# ESP_Grow_Main_V2_2_Pump_NeoPixel.net
KiCad netlist of a schematic drawn in Altium Designer
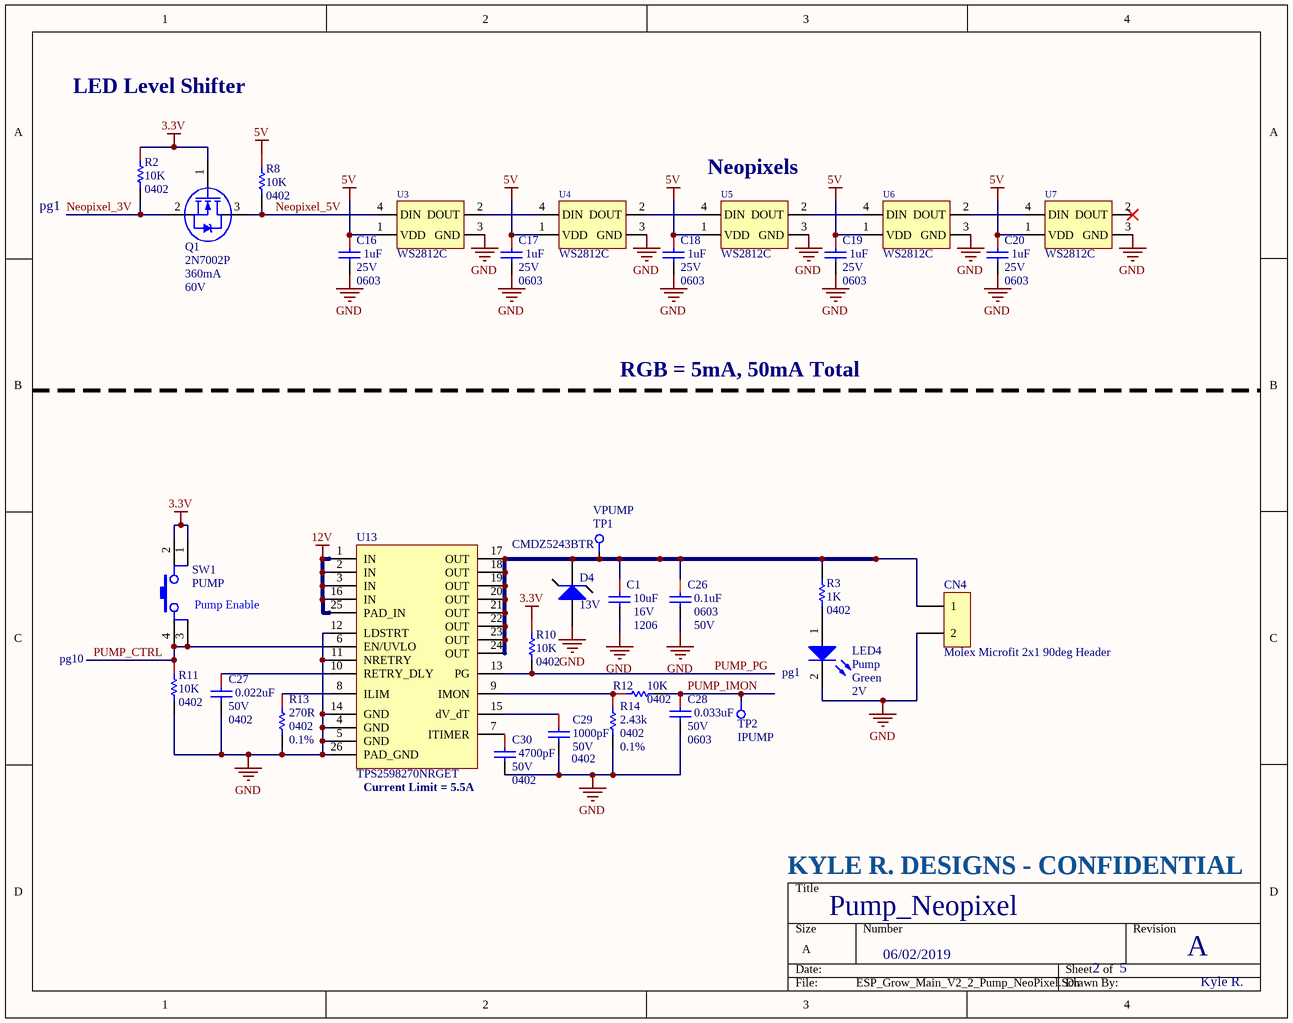
[diagram p0: ESP_Grow_Main_V2_2_Pump_NeoPixel.SchDoc]

(export (version "E")
  (design (tool "Eeschema 10.0.6"))
  (components
    (comp (ref "C1")
      (value "10uF")
      (footprint "CAPC1206(3216)_M")
      (fields (field (name "VOLTAGE - RATED") "16V") (field (name "PACKAGE") "1206"))
      (libsource (lib "Kyle-Passive") (part "CAP CER 10UF 16V 1206"))
    )
    (comp (ref "C16")
      (value "1uF")
      (footprint "CAPC0603(1608)_N")
      (description "1uF 0603 25V")
      (fields
        (field (name "MANUFACTURER") "TDK Corporation")
        (field (name "MANUFACTURER PART NUMBER") "CGA3E1X7R1E105K080AC")
        (field (name "VOLTAGE - RATED") "25V")
        (field (name "PACKAGE / CASE") "0603")
      )
      (libsource (lib "OLogic-Passive") (part "CAP CER 1UF 25V 10% X7R 0603"))
    )
    (comp (ref "C17")
      (value "1uF")
      (footprint "CAPC0603(1608)_N")
      (description "1uF 0603 25V")
      (fields
        (field (name "MANUFACTURER") "TDK Corporation")
        (field (name "MANUFACTURER PART NUMBER") "CGA3E1X7R1E105K080AC")
        (field (name "VOLTAGE - RATED") "25V")
        (field (name "PACKAGE / CASE") "0603")
      )
      (libsource (lib "OLogic-Passive") (part "CAP CER 1UF 25V 10% X7R 0603"))
    )
    (comp (ref "C18")
      (value "1uF")
      (footprint "CAPC0603(1608)_N")
      (description "1uF 0603 25V")
      (fields
        (field (name "MANUFACTURER") "TDK Corporation")
        (field (name "MANUFACTURER PART NUMBER") "CGA3E1X7R1E105K080AC")
        (field (name "VOLTAGE - RATED") "25V")
        (field (name "PACKAGE / CASE") "0603")
      )
      (libsource (lib "OLogic-Passive") (part "CAP CER 1UF 25V 10% X7R 0603"))
    )
    (comp (ref "C19")
      (value "1uF")
      (footprint "CAPC0603(1608)_N")
      (description "1uF 0603 25V")
      (fields
        (field (name "MANUFACTURER") "TDK Corporation")
        (field (name "MANUFACTURER PART NUMBER") "CGA3E1X7R1E105K080AC")
        (field (name "VOLTAGE - RATED") "25V")
        (field (name "PACKAGE / CASE") "0603")
      )
      (libsource (lib "OLogic-Passive") (part "CAP CER 1UF 25V 10% X7R 0603"))
    )
    (comp (ref "C20")
      (value "1uF")
      (footprint "CAPC0603(1608)_N")
      (description "1uF 0603 25V")
      (fields
        (field (name "MANUFACTURER") "TDK Corporation")
        (field (name "MANUFACTURER PART NUMBER") "CGA3E1X7R1E105K080AC")
        (field (name "VOLTAGE - RATED") "25V")
        (field (name "PACKAGE / CASE") "0603")
      )
      (libsource (lib "OLogic-Passive") (part "CAP CER 1UF 25V 10% X7R 0603"))
    )
    (comp (ref "C26")
      (value "0.1uF")
      (footprint "CAPC0603(1608)_L")
      (description "100NF 50V 0603")
      (fields
        (field (name "MANUFACTURER") "YAGEO")
        (field (name "MANUFACTURER PART NUMBER") "CC0603KRX7R9BB104")
        (field (name "CAPACITANCE") "0.1uF")
        (field (name "PACKAGE / CASE") "0603")
        (field (name "VOLTAGE - RATED") "50V")
      )
      (libsource (lib "JLCPCB_Capacitors") (part "0.1uF_0603"))
    )
    (comp (ref "C27")
      (value "0.022uF")
      (footprint "CAPC0402(1005)_N")
      (description "CAP CER 0.022UF 50V X7R 0402")
      (fields
        (field (name "VOLTAGE (RATED)") "50V")
        (field (name "PACKAGE (IMPERIAL)") "0402")
        (field (name "TOLERANCE") "10%")
      )
      (libsource (lib "OLogic Nexus Vault") (part "=Capacitance"))
    )
    (comp (ref "C28")
      (value "0.033uF")
      (footprint "CAPC0603(1608)_L")
      (description "CAP CER 0.033UF 50V X7R 0603")
      (fields
        (field (name "VOLTAGE (RATED)") "50V")
        (field (name "PACKAGE (IMPERIAL)") "0603")
        (field (name "TOLERANCE") "5%")
      )
      (libsource (lib "OLogic Nexus Vault") (part "=Capacitance"))
    )
    (comp (ref "C29")
      (value "1000pF")
      (footprint "CAPC0402(1005)_N")
      (description "1000pF 50V C0G 0402 Kemet 2017")
      (fields
        (field (name "MANUFACTURER") "KEMET")
        (field (name "MANUFACTURER PART NUMBER") "C0402C102J5GACTU")
        (field (name "VOLTAGE - RATED") "50V")
        (field (name "PACKAGE / CASE") "0402")
        (field (name "CAPACITANCE") "1000pF")
      )
      (libsource (lib "OLogic-Passive") (part "CAP CER 1000PF 50V C0G/NP0 0402"))
    )
    (comp (ref "C30")
      (value "4700pF")
      (footprint "CAPC0402(1005)_L")
      (description "CAP CER 4700PF 50V X7R 0402")
      (fields
        (field (name "VOLTAGE (RATED)") "50V")
        (field (name "PACKAGE (IMPERIAL)") "0402")
        (field (name "TOLERANCE") "10%")
      )
      (libsource (lib "OLogic Nexus Vault") (part "=Capacitance"))
    )
    (comp (ref "CN4")
      (value "Molex Microfit 2x1 90deg Header")
      (footprint "Molex 2x1 Microfit 90deg")
      (fields
        (field (name "MANUFACTURER") "Molex Inc")
        (field (name "MANUFACTURER PART NUMBER") "0430450200")
      )
      (libsource (lib "OLogic-Connectors") (part "MICROFIT 3.0 HDR 90deg 2x1CKT"))
    )
    (comp (ref "D4")
      (value "CMDZ5243BTR")
      (footprint "SOD-323")
      (description "DIODE ZENER 13V 250MW SOD323")
      (fields (field (name "TOLERANCE") "5%") (field (name "ZENER VOLTAGE") "13V"))
      (libsource (lib "OLogic Nexus Vault") (part "13V 250mW"))
    )
    (comp (ref "LED4")
      (value "Pump")
      (footprint "SM-LED-0603")
      (description "LED GREEN CLEAR THIN 0603 SMD")
      (fields
        (field (name "MANUFACTURER PART NUMBER") "LTST-C191KGKT")
        (field (name "COLOR") "Green")
        (field (name "MANUFACTURER") "Lite-On Inc")
        (field (name "VOLTAGE - FORWARD (VF) (TYP)") "2V")
      )
      (libsource (lib "OLogic Nexus Vault") (part "OL_LED"))
    )
    (comp (ref "Q1")
      (value "2N7002P")
      (footprint "SOT23")
      (description "MOSFET N-CH 60V 0.36A SOT-23")
      (fields
        (field (name "CONTINUOUS DRAIN CURRENT (ID)") "360mA")
        (field (name "DRAIN TO SOURCE VOLTAGE (VDSS)") "60V")
      )
      (libsource (lib "OLogic Nexus Vault") (part "2N7002P,235"))
    )
    (comp (ref "R2")
      (value "0402WGF1002TCE")
      (footprint "RESC0402(1005)_N")
      (description "10KOHMS ±1% 1/10W 0402")
      (fields (field (name "RESISTANCE") "10K") (field (name "PACKAGE") "0402"))
      (libsource (lib "JLCPCB_Resistors") (part "10k_0402"))
    )
    (comp (ref "R3")
      (value "1K")
      (footprint "RESC0402(1005)_L")
      (description "1K 0402")
      (fields
        (field (name "MANUFACTURER") "Yageo")
        (field (name "MANUFACTURER PART NUMBER") "RC0402FR-071KL")
        (field (name "RESISTANCE") "1K")
        (field (name "PACKAGE / CASE") "0402")
      )
      (libsource (lib "OLogic-Passive") (part "RES 1K OHM 1% 1/16W 0402"))
    )
    (comp (ref "R8")
      (value "0402WGF1002TCE")
      (footprint "RESC0402(1005)_N")
      (description "10KOHMS ±1% 1/10W 0402")
      (fields (field (name "RESISTANCE") "10K") (field (name "PACKAGE") "0402"))
      (libsource (lib "JLCPCB_Resistors") (part "10k_0402"))
    )
    (comp (ref "R10")
      (value "0402WGF1002TCE")
      (footprint "RESC0402(1005)_N")
      (description "10KOHMS ±1% 1/10W 0402")
      (fields (field (name "RESISTANCE") "10K") (field (name "PACKAGE") "0402"))
      (libsource (lib "JLCPCB_Resistors") (part "10k_0402"))
    )
    (comp (ref "R11")
      (value "0402WGF1002TCE")
      (footprint "RESC0402(1005)_N")
      (description "10KOHMS ±1% 1/10W 0402")
      (fields (field (name "RESISTANCE") "10K") (field (name "PACKAGE") "0402"))
      (libsource (lib "JLCPCB_Resistors") (part "10k_0402"))
    )
    (comp (ref "R12")
      (value "0402WGF1002TCE")
      (footprint "RESC0402(1005)_N")
      (description "10KOHMS ±1% 1/10W 0402")
      (fields (field (name "RESISTANCE") "10K") (field (name "PACKAGE") "0402"))
      (libsource (lib "JLCPCB_Resistors") (part "10k_0402"))
    )
    (comp (ref "R13")
      (value "270")
      (footprint "RESC0402(1005)_N")
      (description "RES SMD 270 OHM 0.1% 1/16W 0402")
      (fields
        (field (name "TOLERANCE") "0.1%")
        (field (name "RESISTANCE") "270R")
        (field (name "CASE CODE (IMPERIAL)") "0402")
      )
      (libsource (lib "OLogic Nexus Vault") (part "=Resistance"))
    )
    (comp (ref "R14")
      (value "2.34k")
      (footprint "RESC0402(1005)_L")
      (description "RES SMD 2.43KOHM 0.1% 1/16W 0402")
      (fields
        (field (name "TOLERANCE") "0.1%")
        (field (name "CASE/PACKAGE") "0402")
        (field (name "RESISTANCE") "2.43k")
      )
      (libsource (lib "OLogic Nexus Vault") (part "=Resistance"))
    )
    (comp (ref "SW1")
      (value "PUMP")
      (footprint "SW TACT Red 6mm x 6mm")
      (description "SWITCH TACTILE SPST-NO 0.05A 12V")
      (fields
        (field (name "MANUFACTURER") "C&K")
        (field (name "MANUFACTURER PART NUMBER") "PTS645SM43SMTR92 LFS")
      )
      (libsource (lib "OLogic-Switches") (part "PTS645SM43SMTR92 LFS"))
    )
    (comp (ref "TP1")
      (value "VPUMP")
      (footprint "Pogo-Testpoint")
      (description "Test Point- Current one")
      (libsource (lib "OLogic Nexus Vault") (part "TestPoint"))
    )
    (comp (ref "TP2")
      (value "IPUMP")
      (footprint "Pogo-Testpoint")
      (description "Test Point- Current one")
      (libsource (lib "OLogic Nexus Vault") (part "TestPoint"))
    )
    (comp (ref "U3")
      (value "WS2812C")
      (footprint "WS2812C")
      (description "Serial RGB LED")
      (fields (field (name "VOLTAGE") "3.5V ~ 5.3V"))
      (libsource (lib "Kyle-Diode-Opto-LED") (part "WS2812C"))
    )
    (comp (ref "U4")
      (value "WS2812C")
      (footprint "WS2812C")
      (description "Serial RGB LED")
      (fields (field (name "VOLTAGE") "3.5V ~ 5.3V"))
      (libsource (lib "Kyle-Diode-Opto-LED") (part "WS2812C"))
    )
    (comp (ref "U5")
      (value "WS2812C")
      (footprint "WS2812C")
      (description "Serial RGB LED")
      (fields (field (name "VOLTAGE") "3.5V ~ 5.3V"))
      (libsource (lib "Kyle-Diode-Opto-LED") (part "WS2812C"))
    )
    (comp (ref "U6")
      (value "WS2812C")
      (footprint "WS2812C")
      (description "Serial RGB LED")
      (fields (field (name "VOLTAGE") "3.5V ~ 5.3V"))
      (libsource (lib "Kyle-Diode-Opto-LED") (part "WS2812C"))
    )
    (comp (ref "U7")
      (value "WS2812C")
      (footprint "WS2812C")
      (description "Serial RGB LED")
      (fields (field (name "VOLTAGE") "3.5V ~ 5.3V"))
      (libsource (lib "Kyle-Diode-Opto-LED") (part "WS2812C"))
    )
    (comp (ref "U13")
      (value "TPS2598270NRGET")
      (footprint "VQFN_24")
      (description "15A, 3mohm eFuse with Accurate Current Monitor and Configurable Retry Timers - No UV Lockout")
      (libsource (lib "OLogic Nexus Vault") (part "TPS25982"))
    )
  )
  (nets
    (net (code "1") (name "/Neopixel_3V") (class "Default")
      (node (ref "Q1") (pin "2") (pinfunction "S_2") (pintype "passive"))
      (node (ref "R2") (pin "2") (pinfunction "2_2") (pintype "passive"))
    )
    (net (code "2") (name "/Neopixel_5V") (class "Default")
      (node (ref "Q1") (pin "3") (pinfunction "D_3") (pintype "passive"))
      (node (ref "R8") (pin "2") (pinfunction "2_2") (pintype "passive"))
      (node (ref "U3") (pin "4") (pinfunction "DIN_4") (pintype "power_in"))
    )
    (net (code "3") (name "/PUMP_CTRL") (class "Default")
      (node (ref "R11") (pin "1") (pinfunction "1_1") (pintype "passive"))
      (node (ref "SW1") (pin "3") (pinfunction "3_3") (pintype "passive"))
      (node (ref "SW1") (pin "4") (pinfunction "4_4") (pintype "passive"))
      (node (ref "U13") (pin "6") (pinfunction "EN/UVLO_6") (pintype "power_in"))
    )
    (net (code "4") (name "/PUMP_IMON") (class "Default")
      (node (ref "C28") (pin "1") (pinfunction "1_1") (pintype "passive"))
      (node (ref "R12") (pin "2") (pinfunction "2_2") (pintype "passive"))
      (node (ref "TP2") (pin "1") (pinfunction "1_1") (pintype "passive"))
    )
    (net (code "5") (name "/PUMP_PG") (class "Default")
      (node (ref "R10") (pin "2") (pinfunction "2_2") (pintype "passive"))
      (node (ref "U13") (pin "13") (pinfunction "PG_13") (pintype "power_in"))
    )
    (net (code "6") (name "3.3V") (class "Default")
      (node (ref "Q1") (pin "1") (pinfunction "G_1") (pintype "passive"))
      (node (ref "R10") (pin "1") (pinfunction "1_1") (pintype "passive"))
      (node (ref "R2") (pin "1") (pinfunction "1_1") (pintype "passive"))
      (node (ref "SW1") (pin "1") (pinfunction "1_1") (pintype "passive"))
      (node (ref "SW1") (pin "2") (pinfunction "2_2") (pintype "passive"))
    )
    (net (code "7") (name "5V") (class "Default")
      (node (ref "C16") (pin "1") (pinfunction "1_1") (pintype "passive"))
      (node (ref "C17") (pin "1") (pinfunction "1_1") (pintype "passive"))
      (node (ref "C18") (pin "1") (pinfunction "1_1") (pintype "passive"))
      (node (ref "C19") (pin "1") (pinfunction "1_1") (pintype "passive"))
      (node (ref "C20") (pin "1") (pinfunction "1_1") (pintype "passive"))
      (node (ref "R8") (pin "1") (pinfunction "1_1") (pintype "passive"))
      (node (ref "U3") (pin "1") (pinfunction "VDD_1") (pintype "power_in"))
      (node (ref "U4") (pin "1") (pinfunction "VDD_1") (pintype "power_in"))
      (node (ref "U5") (pin "1") (pinfunction "VDD_1") (pintype "power_in"))
      (node (ref "U6") (pin "1") (pinfunction "VDD_1") (pintype "power_in"))
      (node (ref "U7") (pin "1") (pinfunction "VDD_1") (pintype "power_in"))
    )
    (net (code "8") (name "12V") (class "Default")
      (node (ref "U13") (pin "1") (pinfunction "IN_1") (pintype "power_in"))
      (node (ref "U13") (pin "16") (pinfunction "IN_16") (pintype "power_in"))
      (node (ref "U13") (pin "2") (pinfunction "IN_2") (pintype "power_in"))
      (node (ref "U13") (pin "25") (pinfunction "PAD_IN_25") (pintype "power_in"))
      (node (ref "U13") (pin "3") (pinfunction "IN_3") (pintype "power_in"))
    )
    (net (code "9") (name "GND") (class "Default")
      (node (ref "C1") (pin "2") (pinfunction "2_2") (pintype "passive"))
      (node (ref "C16") (pin "2") (pinfunction "2_2") (pintype "passive"))
      (node (ref "C17") (pin "2") (pinfunction "2_2") (pintype "passive"))
      (node (ref "C18") (pin "2") (pinfunction "2_2") (pintype "passive"))
      (node (ref "C19") (pin "2") (pinfunction "2_2") (pintype "passive"))
      (node (ref "C20") (pin "2") (pinfunction "2_2") (pintype "passive"))
      (node (ref "C26") (pin "2") (pinfunction "2_2") (pintype "passive"))
      (node (ref "C27") (pin "2") (pinfunction "2_2") (pintype "passive"))
      (node (ref "C28") (pin "2") (pinfunction "2_2") (pintype "passive"))
      (node (ref "C29") (pin "2") (pinfunction "2_2") (pintype "passive"))
      (node (ref "C30") (pin "2") (pinfunction "2_2") (pintype "passive"))
      (node (ref "CN4") (pin "2") (pinfunction "2_2") (pintype "passive"))
      (node (ref "D4") (pin "2") (pinfunction "A_2") (pintype "passive"))
      (node (ref "LED4") (pin "2") (pinfunction "K_2") (pintype "passive"))
      (node (ref "R11") (pin "2") (pinfunction "2_2") (pintype "passive"))
      (node (ref "R13") (pin "2") (pinfunction "2_2") (pintype "passive"))
      (node (ref "R14") (pin "2") (pinfunction "2_2") (pintype "passive"))
      (node (ref "U13") (pin "11") (pinfunction "NRETRY_11") (pintype "power_in"))
      (node (ref "U13") (pin "12") (pinfunction "LDSTRT_12") (pintype "power_in"))
      (node (ref "U13") (pin "14") (pinfunction "GND_14") (pintype "power_in"))
      (node (ref "U13") (pin "26") (pinfunction "PAD_GND_26") (pintype "power_in"))
      (node (ref "U13") (pin "4") (pinfunction "GND_4") (pintype "power_in"))
      (node (ref "U13") (pin "5") (pinfunction "GND_5") (pintype "power_in"))
      (node (ref "U3") (pin "3") (pinfunction "GND_3") (pintype "power_in"))
      (node (ref "U4") (pin "3") (pinfunction "GND_3") (pintype "power_in"))
      (node (ref "U5") (pin "3") (pinfunction "GND_3") (pintype "power_in"))
      (node (ref "U6") (pin "3") (pinfunction "GND_3") (pintype "power_in"))
      (node (ref "U7") (pin "3") (pinfunction "GND_3") (pintype "power_in"))
    )
    (net (code "10") (name "Net-(D4-K)") (class "Default")
      (node (ref "C1") (pin "1") (pinfunction "1_1") (pintype "passive"))
      (node (ref "C26") (pin "1") (pinfunction "1_1") (pintype "passive"))
      (node (ref "CN4") (pin "1") (pinfunction "1_1") (pintype "passive"))
      (node (ref "D4") (pin "1") (pinfunction "K_1") (pintype "passive"))
      (node (ref "R3") (pin "2") (pinfunction "2_2") (pintype "passive"))
      (node (ref "TP1") (pin "1") (pinfunction "1_1") (pintype "passive"))
      (node (ref "U13") (pin "17") (pinfunction "OUT_17") (pintype "power_in"))
      (node (ref "U13") (pin "18") (pinfunction "OUT_18") (pintype "power_in"))
      (node (ref "U13") (pin "19") (pinfunction "OUT_19") (pintype "power_in"))
      (node (ref "U13") (pin "20") (pinfunction "OUT_20") (pintype "power_in"))
      (node (ref "U13") (pin "21") (pinfunction "OUT_21") (pintype "power_in"))
      (node (ref "U13") (pin "22") (pinfunction "OUT_22") (pintype "power_in"))
      (node (ref "U13") (pin "23") (pinfunction "OUT_23") (pintype "power_in"))
      (node (ref "U13") (pin "24") (pinfunction "OUT_24") (pintype "power_in"))
    )
    (net (code "11") (name "Net-(LED4-A)") (class "Default")
      (node (ref "LED4") (pin "1") (pinfunction "A_1") (pintype "passive"))
      (node (ref "R3") (pin "1") (pinfunction "1_1") (pintype "passive"))
    )
    (net (code "12") (name "Net-(U3-DOUT)") (class "Default")
      (node (ref "U3") (pin "2") (pinfunction "DOUT_2") (pintype "power_in"))
      (node (ref "U4") (pin "4") (pinfunction "DIN_4") (pintype "power_in"))
    )
    (net (code "13") (name "Net-(U4-DOUT)") (class "Default")
      (node (ref "U4") (pin "2") (pinfunction "DOUT_2") (pintype "power_in"))
      (node (ref "U5") (pin "4") (pinfunction "DIN_4") (pintype "power_in"))
    )
    (net (code "14") (name "Net-(U5-DOUT)") (class "Default")
      (node (ref "U5") (pin "2") (pinfunction "DOUT_2") (pintype "power_in"))
      (node (ref "U6") (pin "4") (pinfunction "DIN_4") (pintype "power_in"))
    )
    (net (code "15") (name "Net-(U6-DOUT)") (class "Default")
      (node (ref "U6") (pin "2") (pinfunction "DOUT_2") (pintype "power_in"))
      (node (ref "U7") (pin "4") (pinfunction "DIN_4") (pintype "power_in"))
    )
    (net (code "16") (name "Net-(U13-ILIM)") (class "Default")
      (node (ref "R13") (pin "1") (pinfunction "1_1") (pintype "passive"))
      (node (ref "U13") (pin "8") (pinfunction "ILIM_8") (pintype "power_in"))
    )
    (net (code "17") (name "Net-(U13-IMON)") (class "Default")
      (node (ref "R12") (pin "1") (pinfunction "1_1") (pintype "passive"))
      (node (ref "R14") (pin "1") (pinfunction "1_1") (pintype "passive"))
      (node (ref "U13") (pin "9") (pinfunction "IMON_9") (pintype "power_in"))
    )
    (net (code "18") (name "Net-(U13-ITIMER)") (class "Default")
      (node (ref "C30") (pin "1") (pinfunction "1_1") (pintype "passive"))
      (node (ref "U13") (pin "7") (pinfunction "ITIMER_7") (pintype "power_in"))
    )
    (net (code "19") (name "Net-(U13-RETRY_DLY)") (class "Default")
      (node (ref "C27") (pin "1") (pinfunction "1_1") (pintype "passive"))
      (node (ref "U13") (pin "10") (pinfunction "RETRY_DLY_10") (pintype "power_in"))
    )
    (net (code "20") (name "Net-(U13-dV_dT)") (class "Default")
      (node (ref "C29") (pin "1") (pinfunction "1_1") (pintype "passive"))
      (node (ref "U13") (pin "15") (pinfunction "dV_dT_15") (pintype "power_in"))
    )
    (net (code "21") (name "unconnected-(U7-DOUT-Pad2)") (class "Default")
      (node (ref "U7") (pin "2") (pinfunction "DOUT_2") (pintype "power_in+no_connect"))
    )
  )
)
